# ADC_Filter.net
KiCad netlist of a schematic drawn in Altium Designer
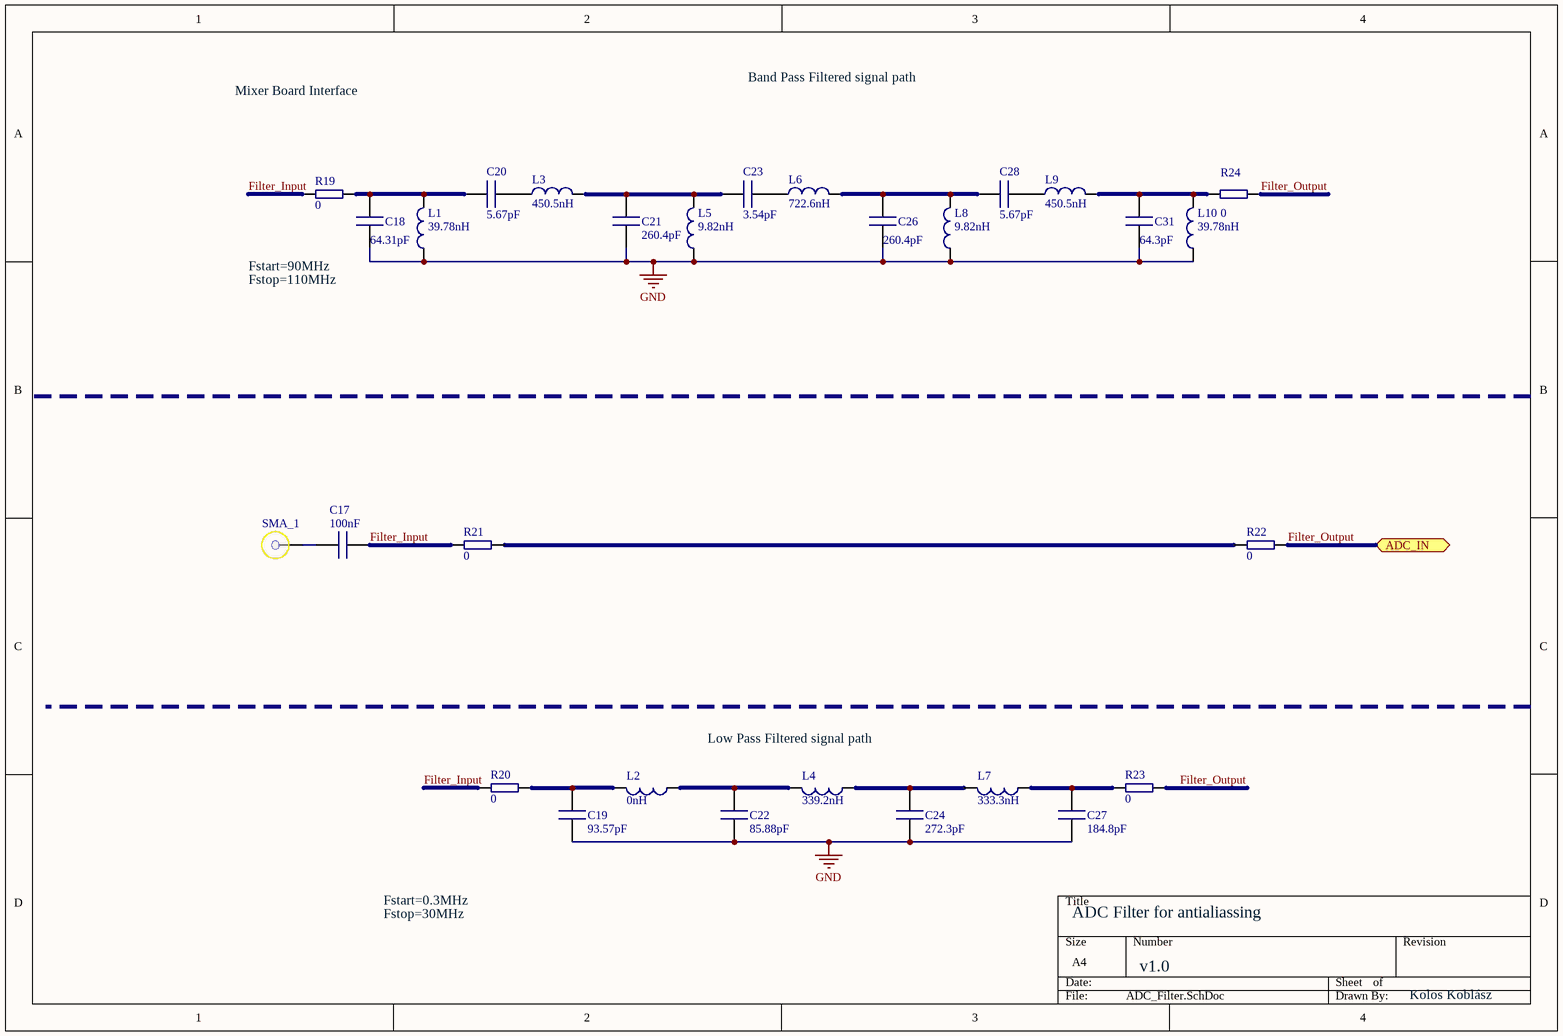
[diagram p0: ADC_Filter.SchDoc]

(export (version "E")
  (design (tool "Eeschema 10.0.6"))
  (components
    (comp (ref "C17")
      (value "100nF")
      (footprint "0805 SMD Passive")
      (description "SMD Capacitor")
      (fields (field (name "Comment") "Cap1"))
      (libsource (lib "RadioProjectSchLib") (part "Cap1"))
    )
    (comp (ref "C18")
      (value "64.31pF")
      (footprint "0805 SMD Passive")
      (description "SMD Capacitor")
      (fields (field (name "Comment") "Cap1"))
      (libsource (lib "RadioProjectSchLib") (part "Cap1"))
    )
    (comp (ref "C19")
      (value "93.57pF")
      (footprint "0805 SMD Passive")
      (description "SMD Capacitor")
      (fields (field (name "Comment") "Cap1"))
      (libsource (lib "RadioProjectSchLib") (part "Cap1"))
    )
    (comp (ref "C20")
      (value "5.67pF")
      (footprint "0805 SMD Passive")
      (description "SMD Capacitor")
      (fields (field (name "Comment") "Cap1"))
      (libsource (lib "RadioProjectSchLib") (part "Cap1"))
    )
    (comp (ref "C21")
      (value "260.4pF")
      (footprint "0805 SMD Passive")
      (description "SMD Capacitor")
      (fields (field (name "Comment") "Cap1"))
      (libsource (lib "RadioProjectSchLib") (part "Cap1"))
    )
    (comp (ref "C22")
      (value "85.88pF")
      (footprint "0805 SMD Passive")
      (description "SMD Capacitor")
      (fields (field (name "Comment") "Cap1"))
      (libsource (lib "RadioProjectSchLib") (part "Cap1"))
    )
    (comp (ref "C23")
      (value "3.54pF")
      (footprint "0805 SMD Passive")
      (description "SMD Capacitor")
      (fields (field (name "Comment") "Cap1"))
      (libsource (lib "RadioProjectSchLib") (part "Cap1"))
    )
    (comp (ref "C24")
      (value "272.3pF")
      (footprint "0805 SMD Passive")
      (description "SMD Capacitor")
      (fields (field (name "Comment") "Cap1"))
      (libsource (lib "RadioProjectSchLib") (part "Cap1"))
    )
    (comp (ref "C26")
      (value "260.4pF")
      (footprint "0805 SMD Passive")
      (description "SMD Capacitor")
      (fields (field (name "Comment") "Cap1"))
      (libsource (lib "RadioProjectSchLib") (part "Cap1"))
    )
    (comp (ref "C27")
      (value "184.8pF")
      (footprint "0805 SMD Passive")
      (description "SMD Capacitor")
      (fields (field (name "Comment") "Cap1"))
      (libsource (lib "RadioProjectSchLib") (part "Cap1"))
    )
    (comp (ref "C28")
      (value "5.67pF")
      (footprint "0805 SMD Passive")
      (description "SMD Capacitor")
      (fields (field (name "Comment") "Cap1"))
      (libsource (lib "RadioProjectSchLib") (part "Cap1"))
    )
    (comp (ref "C31")
      (value "64.3pF")
      (footprint "0805 SMD Passive")
      (description "SMD Capacitor")
      (fields (field (name "Comment") "Cap1"))
      (libsource (lib "RadioProjectSchLib") (part "Cap1"))
    )
    (comp (ref "L1")
      (value "39.78nH")
      (footprint "0805 SMD Passive")
      (description "SMD Inductor")
      (fields (field (name "Comment") "Inductor"))
      (libsource (lib "RadioProjectSchLib") (part "Ind1"))
    )
    (comp (ref "L2")
      (value "0nH")
      (footprint "0805 SMD Passive")
      (description "SMD Inductor")
      (fields (field (name "Comment") "Inductor"))
      (libsource (lib "RadioProjectSchLib") (part "Ind1"))
    )
    (comp (ref "L3")
      (value "450.5nH")
      (footprint "0805 SMD Passive")
      (description "SMD Inductor")
      (fields (field (name "Comment") "Inductor"))
      (libsource (lib "RadioProjectSchLib") (part "Ind1"))
    )
    (comp (ref "L4")
      (value "339.2nH")
      (footprint "0805 SMD Passive")
      (description "SMD Inductor")
      (fields (field (name "Comment") "Inductor"))
      (libsource (lib "RadioProjectSchLib") (part "Ind1"))
    )
    (comp (ref "L5")
      (value "9.82nH")
      (footprint "0805 SMD Passive")
      (description "SMD Inductor")
      (fields (field (name "Comment") "Inductor"))
      (libsource (lib "RadioProjectSchLib") (part "Ind1"))
    )
    (comp (ref "L6")
      (value "722.6nH")
      (footprint "0805 SMD Passive")
      (description "SMD Inductor")
      (fields (field (name "Comment") "Inductor"))
      (libsource (lib "RadioProjectSchLib") (part "Ind1"))
    )
    (comp (ref "L7")
      (value "333.3nH")
      (footprint "0805 SMD Passive")
      (description "SMD Inductor")
      (fields (field (name "Comment") "Inductor"))
      (libsource (lib "RadioProjectSchLib") (part "Ind1"))
    )
    (comp (ref "L8")
      (value "9.82nH")
      (footprint "0805 SMD Passive")
      (description "SMD Inductor")
      (fields (field (name "Comment") "Inductor"))
      (libsource (lib "RadioProjectSchLib") (part "Ind1"))
    )
    (comp (ref "L9")
      (value "450.5nH")
      (footprint "0805 SMD Passive")
      (description "SMD Inductor")
      (fields (field (name "Comment") "Inductor"))
      (libsource (lib "RadioProjectSchLib") (part "Ind1"))
    )
    (comp (ref "L10")
      (value "39.78nH")
      (footprint "0805 SMD Passive")
      (description "SMD Inductor")
      (fields (field (name "Comment") "Inductor"))
      (libsource (lib "RadioProjectSchLib") (part "Ind1"))
    )
    (comp (ref "R19")
      (value "0")
      (footprint "0805 SMD Passive")
      (description "SMD Resistor")
      (fields (field (name "Comment") "Resistor"))
      (libsource (lib "RadioProjectSchLib") (part "Res1"))
    )
    (comp (ref "R20")
      (value "0")
      (footprint "0805 SMD Passive")
      (description "SMD Resistor")
      (fields (field (name "Comment") "Resistor"))
      (libsource (lib "RadioProjectSchLib") (part "Res1"))
    )
    (comp (ref "R21")
      (value "0")
      (footprint "0805 SMD Passive")
      (description "SMD Resistor")
      (fields (field (name "Comment") "Resistor"))
      (libsource (lib "RadioProjectSchLib") (part "Res1"))
    )
    (comp (ref "R22")
      (value "0")
      (footprint "0805 SMD Passive")
      (description "SMD Resistor")
      (fields (field (name "Comment") "Resistor"))
      (libsource (lib "RadioProjectSchLib") (part "Res1"))
    )
    (comp (ref "R23")
      (value "0")
      (footprint "0805 SMD Passive")
      (description "SMD Resistor")
      (fields (field (name "Comment") "Resistor"))
      (libsource (lib "RadioProjectSchLib") (part "Res1"))
    )
    (comp (ref "R24")
      (value "0")
      (footprint "0805 SMD Passive")
      (description "SMD Resistor")
      (fields (field (name "Comment") "Resistor"))
      (libsource (lib "RadioProjectSchLib") (part "Res1"))
    )
    (comp (ref "SMA_1")
      (value "SMA1")
      (footprint "SMA Flange")
      (description "SMA Female")
      (libsource (lib "RadioProjectSchLib") (part "SMA1"))
    )
  )
  (nets
    (net (code "1") (name "/Filter_Input") (class "Default")
      (node (ref "C17") (pin "1") (pinfunction "*_1") (pintype "passive"))
      (node (ref "R19") (pin "2") (pinfunction "*_2") (pintype "passive"))
      (node (ref "R20") (pin "2") (pinfunction "*_2") (pintype "passive"))
      (node (ref "R21") (pin "2") (pinfunction "*_2") (pintype "passive"))
    )
    (net (code "2") (name "/Filter_Output") (class "Default")
      (node (ref "R22") (pin "1") (pinfunction "*_1") (pintype "passive"))
      (node (ref "R23") (pin "1") (pinfunction "*_1") (pintype "passive"))
      (node (ref "R24") (pin "1") (pinfunction "*_1") (pintype "passive"))
    )
    (net (code "3") (name "GND") (class "Default")
      (node (ref "C18") (pin "2") (pinfunction "*_2") (pintype "passive"))
      (node (ref "C19") (pin "1") (pinfunction "*_1") (pintype "passive"))
      (node (ref "C21") (pin "2") (pinfunction "*_2") (pintype "passive"))
      (node (ref "C22") (pin "1") (pinfunction "*_1") (pintype "passive"))
      (node (ref "C24") (pin "1") (pinfunction "*_1") (pintype "passive"))
      (node (ref "C26") (pin "2") (pinfunction "*_2") (pintype "passive"))
      (node (ref "C27") (pin "1") (pinfunction "*_1") (pintype "passive"))
      (node (ref "C31") (pin "2") (pinfunction "*_2") (pintype "passive"))
      (node (ref "L1") (pin "1") (pinfunction "*_1") (pintype "passive"))
      (node (ref "L10") (pin "1") (pinfunction "*_1") (pintype "passive"))
      (node (ref "L5") (pin "1") (pinfunction "*_1") (pintype "passive"))
      (node (ref "L8") (pin "1") (pinfunction "*_1") (pintype "passive"))
    )
    (net (code "4") (name "Net-(C17-*-Pad2)") (class "Default")
      (node (ref "C17") (pin "2") (pinfunction "*_2") (pintype "passive"))
      (node (ref "SMA_1") (pin "1") (pinfunction "1_1") (pintype "passive"))
    )
    (net (code "5") (name "Net-(C18-*-Pad1)") (class "Default")
      (node (ref "C18") (pin "1") (pinfunction "*_1") (pintype "passive"))
      (node (ref "C20") (pin "1") (pinfunction "*_1") (pintype "passive"))
      (node (ref "L1") (pin "2") (pinfunction "*_2") (pintype "passive"))
      (node (ref "R19") (pin "1") (pinfunction "*_1") (pintype "passive"))
    )
    (net (code "6") (name "Net-(C19-*-Pad2)") (class "Default")
      (node (ref "C19") (pin "2") (pinfunction "*_2") (pintype "passive"))
      (node (ref "L2") (pin "2") (pinfunction "*_2") (pintype "passive"))
      (node (ref "R20") (pin "1") (pinfunction "*_1") (pintype "passive"))
    )
    (net (code "7") (name "Net-(C20-*-Pad2)") (class "Default")
      (node (ref "C20") (pin "2") (pinfunction "*_2") (pintype "passive"))
      (node (ref "L3") (pin "1") (pinfunction "*_1") (pintype "passive"))
    )
    (net (code "8") (name "Net-(C21-*-Pad1)") (class "Default")
      (node (ref "C21") (pin "1") (pinfunction "*_1") (pintype "passive"))
      (node (ref "C23") (pin "1") (pinfunction "*_1") (pintype "passive"))
      (node (ref "L3") (pin "2") (pinfunction "*_2") (pintype "passive"))
      (node (ref "L5") (pin "2") (pinfunction "*_2") (pintype "passive"))
    )
    (net (code "9") (name "Net-(C22-*-Pad2)") (class "Default")
      (node (ref "C22") (pin "2") (pinfunction "*_2") (pintype "passive"))
      (node (ref "L2") (pin "1") (pinfunction "*_1") (pintype "passive"))
      (node (ref "L4") (pin "2") (pinfunction "*_2") (pintype "passive"))
    )
    (net (code "10") (name "Net-(C23-*-Pad2)") (class "Default")
      (node (ref "C23") (pin "2") (pinfunction "*_2") (pintype "passive"))
      (node (ref "L6") (pin "1") (pinfunction "*_1") (pintype "passive"))
    )
    (net (code "11") (name "Net-(C24-*-Pad2)") (class "Default")
      (node (ref "C24") (pin "2") (pinfunction "*_2") (pintype "passive"))
      (node (ref "L4") (pin "1") (pinfunction "*_1") (pintype "passive"))
      (node (ref "L7") (pin "2") (pinfunction "*_2") (pintype "passive"))
    )
    (net (code "12") (name "Net-(C26-*-Pad1)") (class "Default")
      (node (ref "C26") (pin "1") (pinfunction "*_1") (pintype "passive"))
      (node (ref "C28") (pin "1") (pinfunction "*_1") (pintype "passive"))
      (node (ref "L6") (pin "2") (pinfunction "*_2") (pintype "passive"))
      (node (ref "L8") (pin "2") (pinfunction "*_2") (pintype "passive"))
    )
    (net (code "13") (name "Net-(C27-*-Pad2)") (class "Default")
      (node (ref "C27") (pin "2") (pinfunction "*_2") (pintype "passive"))
      (node (ref "L7") (pin "1") (pinfunction "*_1") (pintype "passive"))
      (node (ref "R23") (pin "2") (pinfunction "*_2") (pintype "passive"))
    )
    (net (code "14") (name "Net-(C28-*-Pad2)") (class "Default")
      (node (ref "C28") (pin "2") (pinfunction "*_2") (pintype "passive"))
      (node (ref "L9") (pin "1") (pinfunction "*_1") (pintype "passive"))
    )
    (net (code "15") (name "Net-(C31-*-Pad1)") (class "Default")
      (node (ref "C31") (pin "1") (pinfunction "*_1") (pintype "passive"))
      (node (ref "L10") (pin "2") (pinfunction "*_2") (pintype "passive"))
      (node (ref "L9") (pin "2") (pinfunction "*_2") (pintype "passive"))
      (node (ref "R24") (pin "2") (pinfunction "*_2") (pintype "passive"))
    )
    (net (code "16") (name "Net-(R21-*-Pad1)") (class "Default")
      (node (ref "R21") (pin "1") (pinfunction "*_1") (pintype "passive"))
      (node (ref "R22") (pin "2") (pinfunction "*_2") (pintype "passive"))
    )
  )
)
